# LOADCELL.net
KiCad netlist of a schematic drawn in Altium Designer
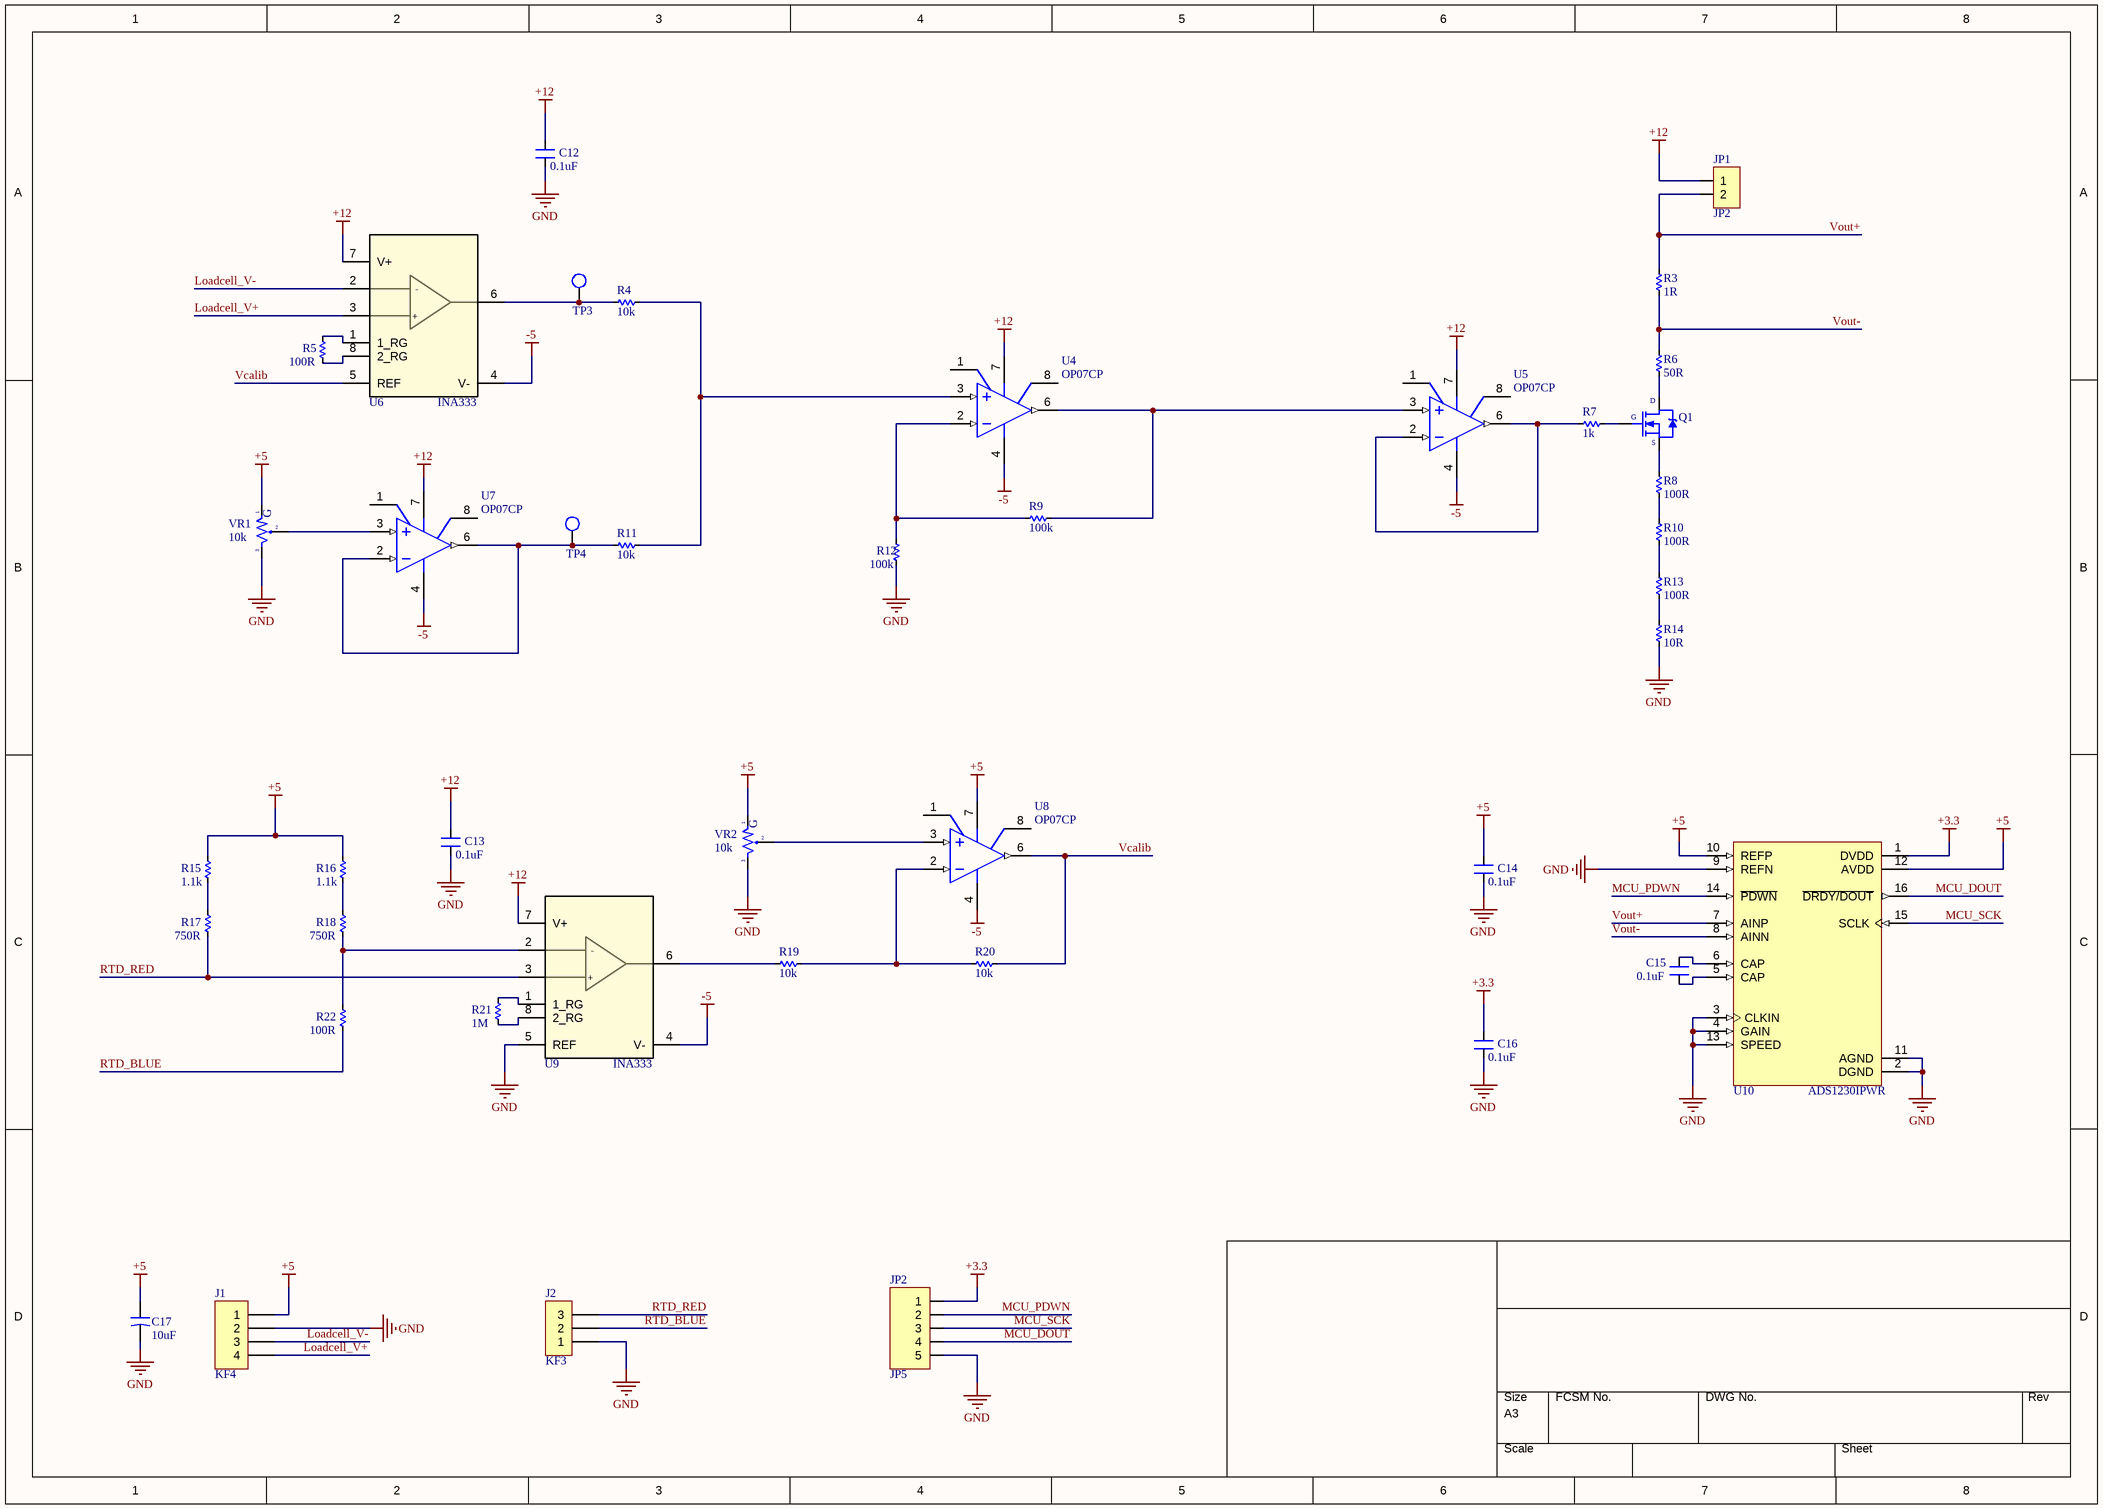
[diagram p0: LOADCELL.SchDoc]

(export (version "E")
  (design (tool "Eeschema 10.0.6"))
  (components
    (comp (ref "C12") (value "0.1uF") (footprint "CN-SMD-0603") (libsource (lib "Library") (part "CN")))
    (comp (ref "C13") (value "0.1uF") (footprint "CN-SMD-0603") (libsource (lib "Library") (part "CN")))
    (comp (ref "C14") (value "0.1uF") (footprint "CN-SMD-0603") (libsource (lib "Library") (part "CN")))
    (comp (ref "C15") (value "0.1uF") (footprint "CN-SMD-0603") (libsource (lib "Library") (part "CN")))
    (comp (ref "C16") (value "0.1uF") (footprint "CN-SMD-0603") (libsource (lib "Library") (part "CN")))
    (comp (ref "C17")
      (value "10uF")
      (footprint "CAP-ALU-SMD-4.5x5x1.4")
      (description "Polarized Capacitor (Axial)")
      (fields (field (name "PUBLISHER") "Altium Limited"))
      (libsource (lib "Library") (part "CN-SMD"))
    )
    (comp (ref "J1")
      (value "KF4")
      (footprint "KF4-5.08T")
      (fields
        (field (name "MANUFACTURER") "Würth Elektronik eiSos GmbH")
        (field (name "PARTNO") "691133710004")
        (field (name "CREATED BY") "Baojun Chen")
      )
      (libsource (lib "Library") (part "KF4"))
    )
    (comp (ref "J2")
      (value "KF3")
      (footprint "KF3-5.08T")
      (fields
        (field (name "MANUFACTURER") "Würth Elektronik eiSos GmbH")
        (field (name "PARTNO") "691103110003")
        (field (name "CREATED BY") "Karrer Zheng")
      )
      (libsource (lib "Library") (part "KF3"))
    )
    (comp (ref "JP1")
      (value "JP2")
      (footprint "JP2-CLOSED")
      (description "WR-PHD 2.54 mm Angled Socket Header")
      (fields
        (field (name "MANUFACTURER") "Würth Elektronik eiSos GmbH")
        (field (name "PARTNO") "613002143121")
        (field (name "CREATED BY") "Karrer Zheng")
      )
      (libsource (lib "Library") (part "JP2"))
    )
    (comp (ref "JP2")
      (value "JP5")
      (footprint "JP5-D1T")
      (description "WR-PHD 2.54 mm Angled Socket Header")
      (fields
        (field (name "MANUFACTURER") "Würth Elektronik eiSos GmbH")
        (field (name "PARTNO") "613005143121")
        (field (name "CREATED BY") "Karrer Zheng")
      )
      (libsource (lib "Library") (part "JP5"))
    )
    (comp (ref "Q1")
      (value "AO3400")
      (footprint "SOT23-123")
      (description "N-MOS 30V 5.8A")
      (libsource (lib "Library") (part "AO3400"))
    )
    (comp (ref "R3")
      (value "1R")
      (footprint "RES-SMD-0603")
      (description "Resistor")
      (fields
        (field (name "MANUFACTURER") "Generic Components")
        (field (name "PUBLISHER") "Altium Hobart Technology Centre")
      )
      (libsource (lib "Library") (part "Res-SMD"))
    )
    (comp (ref "R4")
      (value "10k")
      (footprint "RES-SMD-0603")
      (description "Resistor")
      (fields
        (field (name "MANUFACTURER") "Generic Components")
        (field (name "PUBLISHER") "Altium Hobart Technology Centre")
      )
      (libsource (lib "Library") (part "Res-SMD"))
    )
    (comp (ref "R5")
      (value "100R")
      (footprint "RES-SMD-0603")
      (description "Resistor")
      (fields
        (field (name "MANUFACTURER") "Generic Components")
        (field (name "PUBLISHER") "Altium Hobart Technology Centre")
      )
      (libsource (lib "Library") (part "Res-SMD"))
    )
    (comp (ref "R6")
      (value "50R")
      (footprint "RES-SMD-0603")
      (description "Resistor")
      (fields
        (field (name "MANUFACTURER") "Generic Components")
        (field (name "PUBLISHER") "Altium Hobart Technology Centre")
      )
      (libsource (lib "Library") (part "Res-SMD"))
    )
    (comp (ref "R7")
      (value "1k")
      (footprint "RES-SMD-0603")
      (description "Resistor")
      (fields
        (field (name "MANUFACTURER") "Generic Components")
        (field (name "PUBLISHER") "Altium Hobart Technology Centre")
      )
      (libsource (lib "Library") (part "Res-SMD"))
    )
    (comp (ref "R8")
      (value "100R")
      (footprint "RES-SMD-0603")
      (description "Resistor")
      (fields
        (field (name "MANUFACTURER") "Generic Components")
        (field (name "PUBLISHER") "Altium Hobart Technology Centre")
      )
      (libsource (lib "Library") (part "Res-SMD"))
    )
    (comp (ref "R9")
      (value "100k")
      (footprint "RES-SMD-0603")
      (description "Resistor")
      (fields
        (field (name "MANUFACTURER") "Generic Components")
        (field (name "PUBLISHER") "Altium Hobart Technology Centre")
      )
      (libsource (lib "Library") (part "Res-SMD"))
    )
    (comp (ref "R10")
      (value "100R")
      (footprint "RES-SMD-0603")
      (description "Resistor")
      (fields
        (field (name "MANUFACTURER") "Generic Components")
        (field (name "PUBLISHER") "Altium Hobart Technology Centre")
      )
      (libsource (lib "Library") (part "Res-SMD"))
    )
    (comp (ref "R11")
      (value "10k")
      (footprint "RES-SMD-0603")
      (description "Resistor")
      (fields
        (field (name "MANUFACTURER") "Generic Components")
        (field (name "PUBLISHER") "Altium Hobart Technology Centre")
      )
      (libsource (lib "Library") (part "Res-SMD"))
    )
    (comp (ref "R12")
      (value "100k")
      (footprint "RES-SMD-0603")
      (description "Resistor")
      (fields
        (field (name "MANUFACTURER") "Generic Components")
        (field (name "PUBLISHER") "Altium Hobart Technology Centre")
      )
      (libsource (lib "Library") (part "Res-SMD"))
    )
    (comp (ref "R13")
      (value "100R")
      (footprint "RES-SMD-0603")
      (description "Resistor")
      (fields
        (field (name "MANUFACTURER") "Generic Components")
        (field (name "PUBLISHER") "Altium Hobart Technology Centre")
      )
      (libsource (lib "Library") (part "Res-SMD"))
    )
    (comp (ref "R14")
      (value "10R")
      (footprint "RES-SMD-0603")
      (description "Resistor")
      (fields
        (field (name "MANUFACTURER") "Generic Components")
        (field (name "PUBLISHER") "Altium Hobart Technology Centre")
      )
      (libsource (lib "Library") (part "Res-SMD"))
    )
    (comp (ref "R15")
      (value "1.1k")
      (footprint "RES-SMD-0603")
      (description "Resistor")
      (fields
        (field (name "MANUFACTURER") "Generic Components")
        (field (name "PUBLISHER") "Altium Hobart Technology Centre")
      )
      (libsource (lib "Library") (part "Res-SMD"))
    )
    (comp (ref "R16")
      (value "1.1k")
      (footprint "RES-SMD-0603")
      (description "Resistor")
      (fields
        (field (name "MANUFACTURER") "Generic Components")
        (field (name "PUBLISHER") "Altium Hobart Technology Centre")
      )
      (libsource (lib "Library") (part "Res-SMD"))
    )
    (comp (ref "R17")
      (value "750R")
      (footprint "RES-SMD-0603")
      (description "Resistor")
      (fields
        (field (name "MANUFACTURER") "Generic Components")
        (field (name "PUBLISHER") "Altium Hobart Technology Centre")
      )
      (libsource (lib "Library") (part "Res-SMD"))
    )
    (comp (ref "R18")
      (value "750R")
      (footprint "RES-SMD-0603")
      (description "Resistor")
      (fields
        (field (name "MANUFACTURER") "Generic Components")
        (field (name "PUBLISHER") "Altium Hobart Technology Centre")
      )
      (libsource (lib "Library") (part "Res-SMD"))
    )
    (comp (ref "R19")
      (value "10k")
      (footprint "RES-SMD-0603")
      (description "Resistor")
      (fields
        (field (name "MANUFACTURER") "Generic Components")
        (field (name "PUBLISHER") "Altium Hobart Technology Centre")
      )
      (libsource (lib "Library") (part "Res-SMD"))
    )
    (comp (ref "R20")
      (value "10k")
      (footprint "RES-SMD-0603")
      (description "Resistor")
      (fields
        (field (name "MANUFACTURER") "Generic Components")
        (field (name "PUBLISHER") "Altium Hobart Technology Centre")
      )
      (libsource (lib "Library") (part "Res-SMD"))
    )
    (comp (ref "R21")
      (value "1M")
      (footprint "RES-SMD-0603")
      (description "Resistor")
      (fields
        (field (name "MANUFACTURER") "Generic Components")
        (field (name "PUBLISHER") "Altium Hobart Technology Centre")
      )
      (libsource (lib "Library") (part "Res-SMD"))
    )
    (comp (ref "R22")
      (value "100R")
      (footprint "RES-SMD-0603")
      (description "Resistor")
      (fields
        (field (name "MANUFACTURER") "Generic Components")
        (field (name "PUBLISHER") "Altium Hobart Technology Centre")
      )
      (libsource (lib "Library") (part "Res-SMD"))
    )
    (comp (ref "TP3")
      (value "Test-Point")
      (footprint "TESTPOINT")
      (libsource (lib "Library") (part "Test-Point"))
    )
    (comp (ref "TP4")
      (value "Test-Point")
      (footprint "TESTPOINT")
      (libsource (lib "Library") (part "Test-Point"))
    )
    (comp (ref "U4")
      (value "OP07CP")
      (footprint "SO8")
      (description "Ultra-Low Offset Voltage Operational Amplifier")
      (fields (field (name "PUBLISHER") "Altium Limited"))
      (libsource (lib "Library") (part "OP07CP"))
    )
    (comp (ref "U5")
      (value "OP07CP")
      (footprint "SO8")
      (description "Ultra-Low Offset Voltage Operational Amplifier")
      (fields (field (name "PUBLISHER") "Altium Limited"))
      (libsource (lib "Library") (part "OP07CP"))
    )
    (comp (ref "U6") (value "INA333") (footprint "VSSOP8") (libsource (lib "Library") (part "INA333")))
    (comp (ref "U7")
      (value "OP07CP")
      (footprint "SO8")
      (description "Ultra-Low Offset Voltage Operational Amplifier")
      (fields (field (name "PUBLISHER") "Altium Limited"))
      (libsource (lib "Library") (part "OP07CP"))
    )
    (comp (ref "U8")
      (value "OP07CP")
      (footprint "SO8")
      (description "Ultra-Low Offset Voltage Operational Amplifier")
      (fields (field (name "PUBLISHER") "Altium Limited"))
      (libsource (lib "Library") (part "OP07CP"))
    )
    (comp (ref "U9") (value "INA333") (footprint "VSSOP8") (libsource (lib "Library") (part "INA333")))
    (comp (ref "U10")
      (value "ADS1230IPWR")
      (footprint "TSSOP16")
      (libsource (lib "Library") (part "ADS1230IPWR"))
    )
    (comp (ref "VR1")
      (value "10k")
      (footprint "VR-S2")
      (description "Var Resistor")
      (libsource (lib "Library") (part "VR-S"))
    )
    (comp (ref "VR2")
      (value "10k")
      (footprint "VR-S2")
      (description "Var Resistor")
      (libsource (lib "Library") (part "VR-S"))
    )
  )
  (nets
    (net (code "1") (name "+3.3") (class "Default")
      (node (ref "C16") (pin "1") (pinfunction "1_1") (pintype "passive"))
      (node (ref "JP2") (pin "1") (pinfunction "1_1") (pintype "passive"))
      (node (ref "U10") (pin "1") (pinfunction "DVDD_1") (pintype "power_in"))
    )
    (net (code "2") (name "+5") (class "Default")
      (node (ref "C14") (pin "1") (pinfunction "1_1") (pintype "passive"))
      (node (ref "C17") (pin "1") (pinfunction "1_1") (pintype "passive"))
      (node (ref "J1") (pin "1") (pinfunction "1_1") (pintype "passive"))
      (node (ref "R15") (pin "1") (pinfunction "1_1") (pintype "passive"))
      (node (ref "R16") (pin "1") (pinfunction "1_1") (pintype "passive"))
      (node (ref "U10") (pin "10") (pinfunction "REFP_10") (pintype "input"))
      (node (ref "U10") (pin "12") (pinfunction "AVDD_12") (pintype "power_in"))
      (node (ref "U8") (pin "7") (pinfunction "V+_7") (pintype "power_in"))
      (node (ref "VR1") (pin "1") (pinfunction "1_1") (pintype "passive"))
      (node (ref "VR2") (pin "1") (pinfunction "1_1") (pintype "passive"))
    )
    (net (code "3") (name "+12") (class "Default")
      (node (ref "C12") (pin "1") (pinfunction "1_1") (pintype "passive"))
      (node (ref "C13") (pin "1") (pinfunction "1_1") (pintype "passive"))
      (node (ref "JP1") (pin "1") (pinfunction "1_1") (pintype "passive"))
      (node (ref "U4") (pin "7") (pinfunction "V+_7") (pintype "power_in"))
      (node (ref "U5") (pin "7") (pinfunction "V+_7") (pintype "power_in"))
      (node (ref "U6") (pin "7") (pinfunction "V+_7") (pintype "power_in"))
      (node (ref "U7") (pin "7") (pinfunction "V+_7") (pintype "power_in"))
      (node (ref "U9") (pin "7") (pinfunction "V+_7") (pintype "power_in"))
    )
    (net (code "4") (name "-5") (class "Default")
      (node (ref "U4") (pin "4") (pinfunction "V-_4") (pintype "power_in"))
      (node (ref "U5") (pin "4") (pinfunction "V-_4") (pintype "power_in"))
      (node (ref "U6") (pin "4") (pinfunction "V-_4") (pintype "power_in"))
      (node (ref "U7") (pin "4") (pinfunction "V-_4") (pintype "power_in"))
      (node (ref "U8") (pin "4") (pinfunction "V-_4") (pintype "power_in"))
      (node (ref "U9") (pin "4") (pinfunction "V-_4") (pintype "power_in"))
    )
    (net (code "5") (name "/Loadcell_V+") (class "Default")
      (node (ref "J1") (pin "4") (pinfunction "4_4") (pintype "passive"))
      (node (ref "U6") (pin "3") (pinfunction "VIN+_3") (pintype "tri_state"))
    )
    (net (code "6") (name "/Loadcell_V-") (class "Default")
      (node (ref "J1") (pin "3") (pinfunction "3_3") (pintype "passive"))
      (node (ref "U6") (pin "2") (pinfunction "VIN-_2") (pintype "tri_state"))
    )
    (net (code "7") (name "/MCU_DOUT") (class "Default")
      (node (ref "JP2") (pin "4") (pinfunction "4_4") (pintype "passive"))
      (node (ref "U10") (pin "16") (pinfunction "~{DRDY/DOUT}_16") (pintype "output"))
    )
    (net (code "8") (name "/MCU_PDWN") (class "Default")
      (node (ref "JP2") (pin "2") (pinfunction "2_2") (pintype "passive"))
      (node (ref "U10") (pin "14") (pinfunction "~{PDWN}_14") (pintype "input"))
    )
    (net (code "9") (name "/MCU_SCK") (class "Default")
      (node (ref "JP2") (pin "3") (pinfunction "3_3") (pintype "passive"))
      (node (ref "U10") (pin "15") (pinfunction "SCLK_15") (pintype "input"))
    )
    (net (code "10") (name "/RTD_BLUE") (class "Default")
      (node (ref "J2") (pin "2") (pinfunction "2_2") (pintype "passive"))
      (node (ref "R22") (pin "2") (pinfunction "2_2") (pintype "passive"))
    )
    (net (code "11") (name "/RTD_RED") (class "Default")
      (node (ref "J2") (pin "3") (pinfunction "3_3") (pintype "passive"))
      (node (ref "R17") (pin "2") (pinfunction "2_2") (pintype "passive"))
      (node (ref "U9") (pin "3") (pinfunction "VIN+_3") (pintype "tri_state"))
    )
    (net (code "12") (name "/Vcalib") (class "Default")
      (node (ref "R20") (pin "2") (pinfunction "2_2") (pintype "passive"))
      (node (ref "U6") (pin "5") (pinfunction "REF_5") (pintype "passive"))
      (node (ref "U8") (pin "6") (pinfunction "OUT_6") (pintype "output"))
    )
    (net (code "13") (name "/Vout+") (class "Default")
      (node (ref "JP1") (pin "2") (pinfunction "2_2") (pintype "passive"))
      (node (ref "R3") (pin "2") (pinfunction "2_2") (pintype "passive"))
      (node (ref "U10") (pin "7") (pinfunction "AINP_7") (pintype "input"))
    )
    (net (code "14") (name "/Vout-") (class "Default")
      (node (ref "R3") (pin "1") (pinfunction "1_1") (pintype "passive"))
      (node (ref "R6") (pin "2") (pinfunction "2_2") (pintype "passive"))
      (node (ref "U10") (pin "8") (pinfunction "AINN_8") (pintype "input"))
    )
    (net (code "15") (name "GND") (class "Default")
      (node (ref "C12") (pin "2") (pinfunction "2_2") (pintype "passive"))
      (node (ref "C13") (pin "2") (pinfunction "2_2") (pintype "passive"))
      (node (ref "C14") (pin "2") (pinfunction "2_2") (pintype "passive"))
      (node (ref "C16") (pin "2") (pinfunction "2_2") (pintype "passive"))
      (node (ref "C17") (pin "2") (pinfunction "2_2") (pintype "passive"))
      (node (ref "J1") (pin "2") (pinfunction "2_2") (pintype "passive"))
      (node (ref "J2") (pin "1") (pinfunction "1_1") (pintype "passive"))
      (node (ref "JP2") (pin "5") (pinfunction "5_5") (pintype "passive"))
      (node (ref "R12") (pin "2") (pinfunction "2_2") (pintype "passive"))
      (node (ref "R14") (pin "1") (pinfunction "1_1") (pintype "passive"))
      (node (ref "U10") (pin "11") (pinfunction "AGND_11") (pintype "power_in"))
      (node (ref "U10") (pin "13") (pinfunction "SPEED_13") (pintype "input"))
      (node (ref "U10") (pin "2") (pinfunction "DGND_2") (pintype "power_in"))
      (node (ref "U10") (pin "3") (pinfunction "CLKIN_3") (pintype "input"))
      (node (ref "U10") (pin "4") (pinfunction "GAIN_4") (pintype "input"))
      (node (ref "U10") (pin "9") (pinfunction "REFN_9") (pintype "input"))
      (node (ref "U9") (pin "5") (pinfunction "REF_5") (pintype "passive"))
      (node (ref "VR1") (pin "3") (pinfunction "3_3") (pintype "passive"))
      (node (ref "VR2") (pin "3") (pinfunction "3_3") (pintype "passive"))
    )
    (net (code "16") (name "Net-(C15-Pad1)") (class "Default")
      (node (ref "C15") (pin "1") (pinfunction "1_1") (pintype "passive"))
      (node (ref "U10") (pin "6") (pinfunction "CAP_6") (pintype "input"))
    )
    (net (code "17") (name "Net-(C15-Pad2)") (class "Default")
      (node (ref "C15") (pin "2") (pinfunction "2_2") (pintype "passive"))
      (node (ref "U10") (pin "5") (pinfunction "CAP_5") (pintype "input"))
    )
    (net (code "18") (name "Net-(Q1-D)") (class "Default")
      (node (ref "Q1") (pin "2") (pinfunction "D_2") (pintype "passive"))
      (node (ref "R6") (pin "1") (pinfunction "1_1") (pintype "passive"))
    )
    (net (code "19") (name "Net-(Q1-G)") (class "Default")
      (node (ref "Q1") (pin "1") (pinfunction "G_1") (pintype "passive"))
      (node (ref "R7") (pin "2") (pinfunction "2_2") (pintype "passive"))
    )
    (net (code "20") (name "Net-(Q1-S)") (class "Default")
      (node (ref "Q1") (pin "3") (pinfunction "S_3") (pintype "passive"))
      (node (ref "R8") (pin "2") (pinfunction "2_2") (pintype "passive"))
    )
    (net (code "21") (name "Net-(R10-Pad1)") (class "Default")
      (node (ref "R10") (pin "1") (pinfunction "1_1") (pintype "passive"))
      (node (ref "R13") (pin "2") (pinfunction "2_2") (pintype "passive"))
    )
    (net (code "22") (name "Net-(R10-Pad2)") (class "Default")
      (node (ref "R10") (pin "2") (pinfunction "2_2") (pintype "passive"))
      (node (ref "R8") (pin "1") (pinfunction "1_1") (pintype "passive"))
    )
    (net (code "23") (name "Net-(R13-Pad1)") (class "Default")
      (node (ref "R13") (pin "1") (pinfunction "1_1") (pintype "passive"))
      (node (ref "R14") (pin "2") (pinfunction "2_2") (pintype "passive"))
    )
    (net (code "24") (name "Net-(R15-Pad2)") (class "Default")
      (node (ref "R15") (pin "2") (pinfunction "2_2") (pintype "passive"))
      (node (ref "R17") (pin "1") (pinfunction "1_1") (pintype "passive"))
    )
    (net (code "25") (name "Net-(R16-Pad2)") (class "Default")
      (node (ref "R16") (pin "2") (pinfunction "2_2") (pintype "passive"))
      (node (ref "R18") (pin "1") (pinfunction "1_1") (pintype "passive"))
    )
    (net (code "26") (name "Net-(U4-IN+)") (class "Default")
      (node (ref "R11") (pin "2") (pinfunction "2_2") (pintype "passive"))
      (node (ref "R4") (pin "2") (pinfunction "2_2") (pintype "passive"))
      (node (ref "U4") (pin "3") (pinfunction "IN+_3") (pintype "input"))
    )
    (net (code "27") (name "Net-(U4-IN-)") (class "Default")
      (node (ref "R12") (pin "1") (pinfunction "1_1") (pintype "passive"))
      (node (ref "R9") (pin "1") (pinfunction "1_1") (pintype "passive"))
      (node (ref "U4") (pin "2") (pinfunction "IN-_2") (pintype "input"))
    )
    (net (code "28") (name "Net-(U4-OUT)") (class "Default")
      (node (ref "R9") (pin "2") (pinfunction "2_2") (pintype "passive"))
      (node (ref "U4") (pin "6") (pinfunction "OUT_6") (pintype "output"))
      (node (ref "U5") (pin "3") (pinfunction "IN+_3") (pintype "input"))
    )
    (net (code "29") (name "Net-(U5-IN-)") (class "Default")
      (node (ref "R7") (pin "1") (pinfunction "1_1") (pintype "passive"))
      (node (ref "U5") (pin "2") (pinfunction "IN-_2") (pintype "input"))
      (node (ref "U5") (pin "6") (pinfunction "OUT_6") (pintype "output"))
    )
    (net (code "30") (name "Net-(U6-1_RG)") (class "Default")
      (node (ref "R5") (pin "1") (pinfunction "1_1") (pintype "passive"))
      (node (ref "U6") (pin "1") (pinfunction "1_RG_1") (pintype "passive"))
    )
    (net (code "31") (name "Net-(U6-2_RG)") (class "Default")
      (node (ref "R5") (pin "2") (pinfunction "2_2") (pintype "passive"))
      (node (ref "U6") (pin "8") (pinfunction "2_RG_8") (pintype "passive"))
    )
    (net (code "32") (name "Net-(U6-VOUT)") (class "Default")
      (node (ref "R4") (pin "1") (pinfunction "1_1") (pintype "passive"))
      (node (ref "TP3") (pin "1") (pinfunction "1_1") (pintype "passive"))
      (node (ref "U6") (pin "6") (pinfunction "VOUT_6") (pintype "passive"))
    )
    (net (code "33") (name "Net-(U7-IN+)") (class "Default")
      (node (ref "U7") (pin "3") (pinfunction "IN+_3") (pintype "input"))
      (node (ref "VR1") (pin "2") (pinfunction "2_2") (pintype "passive"))
    )
    (net (code "34") (name "Net-(U7-IN-)") (class "Default")
      (node (ref "R11") (pin "1") (pinfunction "1_1") (pintype "passive"))
      (node (ref "TP4") (pin "1") (pinfunction "1_1") (pintype "passive"))
      (node (ref "U7") (pin "2") (pinfunction "IN-_2") (pintype "input"))
      (node (ref "U7") (pin "6") (pinfunction "OUT_6") (pintype "output"))
    )
    (net (code "35") (name "Net-(U8-IN+)") (class "Default")
      (node (ref "U8") (pin "3") (pinfunction "IN+_3") (pintype "input"))
      (node (ref "VR2") (pin "2") (pinfunction "2_2") (pintype "passive"))
    )
    (net (code "36") (name "Net-(U8-IN-)") (class "Default")
      (node (ref "R19") (pin "2") (pinfunction "2_2") (pintype "passive"))
      (node (ref "R20") (pin "1") (pinfunction "1_1") (pintype "passive"))
      (node (ref "U8") (pin "2") (pinfunction "IN-_2") (pintype "input"))
    )
    (net (code "37") (name "Net-(U9-1_RG)") (class "Default")
      (node (ref "R21") (pin "1") (pinfunction "1_1") (pintype "passive"))
      (node (ref "U9") (pin "1") (pinfunction "1_RG_1") (pintype "passive"))
    )
    (net (code "38") (name "Net-(U9-2_RG)") (class "Default")
      (node (ref "R21") (pin "2") (pinfunction "2_2") (pintype "passive"))
      (node (ref "U9") (pin "8") (pinfunction "2_RG_8") (pintype "passive"))
    )
    (net (code "39") (name "Net-(U9-VIN-)") (class "Default")
      (node (ref "R18") (pin "2") (pinfunction "2_2") (pintype "passive"))
      (node (ref "R22") (pin "1") (pinfunction "1_1") (pintype "passive"))
      (node (ref "U9") (pin "2") (pinfunction "VIN-_2") (pintype "tri_state"))
    )
    (net (code "40") (name "Net-(U9-VOUT)") (class "Default")
      (node (ref "R19") (pin "1") (pinfunction "1_1") (pintype "passive"))
      (node (ref "U9") (pin "6") (pinfunction "VOUT_6") (pintype "passive"))
    )
    (net (code "41") (name "unconnected-(U4-VOSTRIM-Pad1)") (class "Default")
      (node (ref "U4") (pin "1") (pinfunction "VOSTRIM_1") (pintype "passive"))
    )
    (net (code "42") (name "unconnected-(U4-VOSTRIM-Pad8)") (class "Default")
      (node (ref "U4") (pin "8") (pinfunction "VOSTRIM_8") (pintype "passive"))
    )
    (net (code "43") (name "unconnected-(U5-VOSTRIM-Pad1)") (class "Default")
      (node (ref "U5") (pin "1") (pinfunction "VOSTRIM_1") (pintype "passive"))
    )
    (net (code "44") (name "unconnected-(U5-VOSTRIM-Pad8)") (class "Default")
      (node (ref "U5") (pin "8") (pinfunction "VOSTRIM_8") (pintype "passive"))
    )
    (net (code "45") (name "unconnected-(U7-VOSTRIM-Pad1)") (class "Default")
      (node (ref "U7") (pin "1") (pinfunction "VOSTRIM_1") (pintype "passive"))
    )
    (net (code "46") (name "unconnected-(U7-VOSTRIM-Pad8)") (class "Default")
      (node (ref "U7") (pin "8") (pinfunction "VOSTRIM_8") (pintype "passive"))
    )
    (net (code "47") (name "unconnected-(U8-VOSTRIM-Pad1)") (class "Default")
      (node (ref "U8") (pin "1") (pinfunction "VOSTRIM_1") (pintype "passive"))
    )
    (net (code "48") (name "unconnected-(U8-VOSTRIM-Pad8)") (class "Default")
      (node (ref "U8") (pin "8") (pinfunction "VOSTRIM_8") (pintype "passive"))
    )
  )
)
